# SCH_project_BMO_2026-04-16.net
KiCad netlist of a schematic drawn in EasyEDA
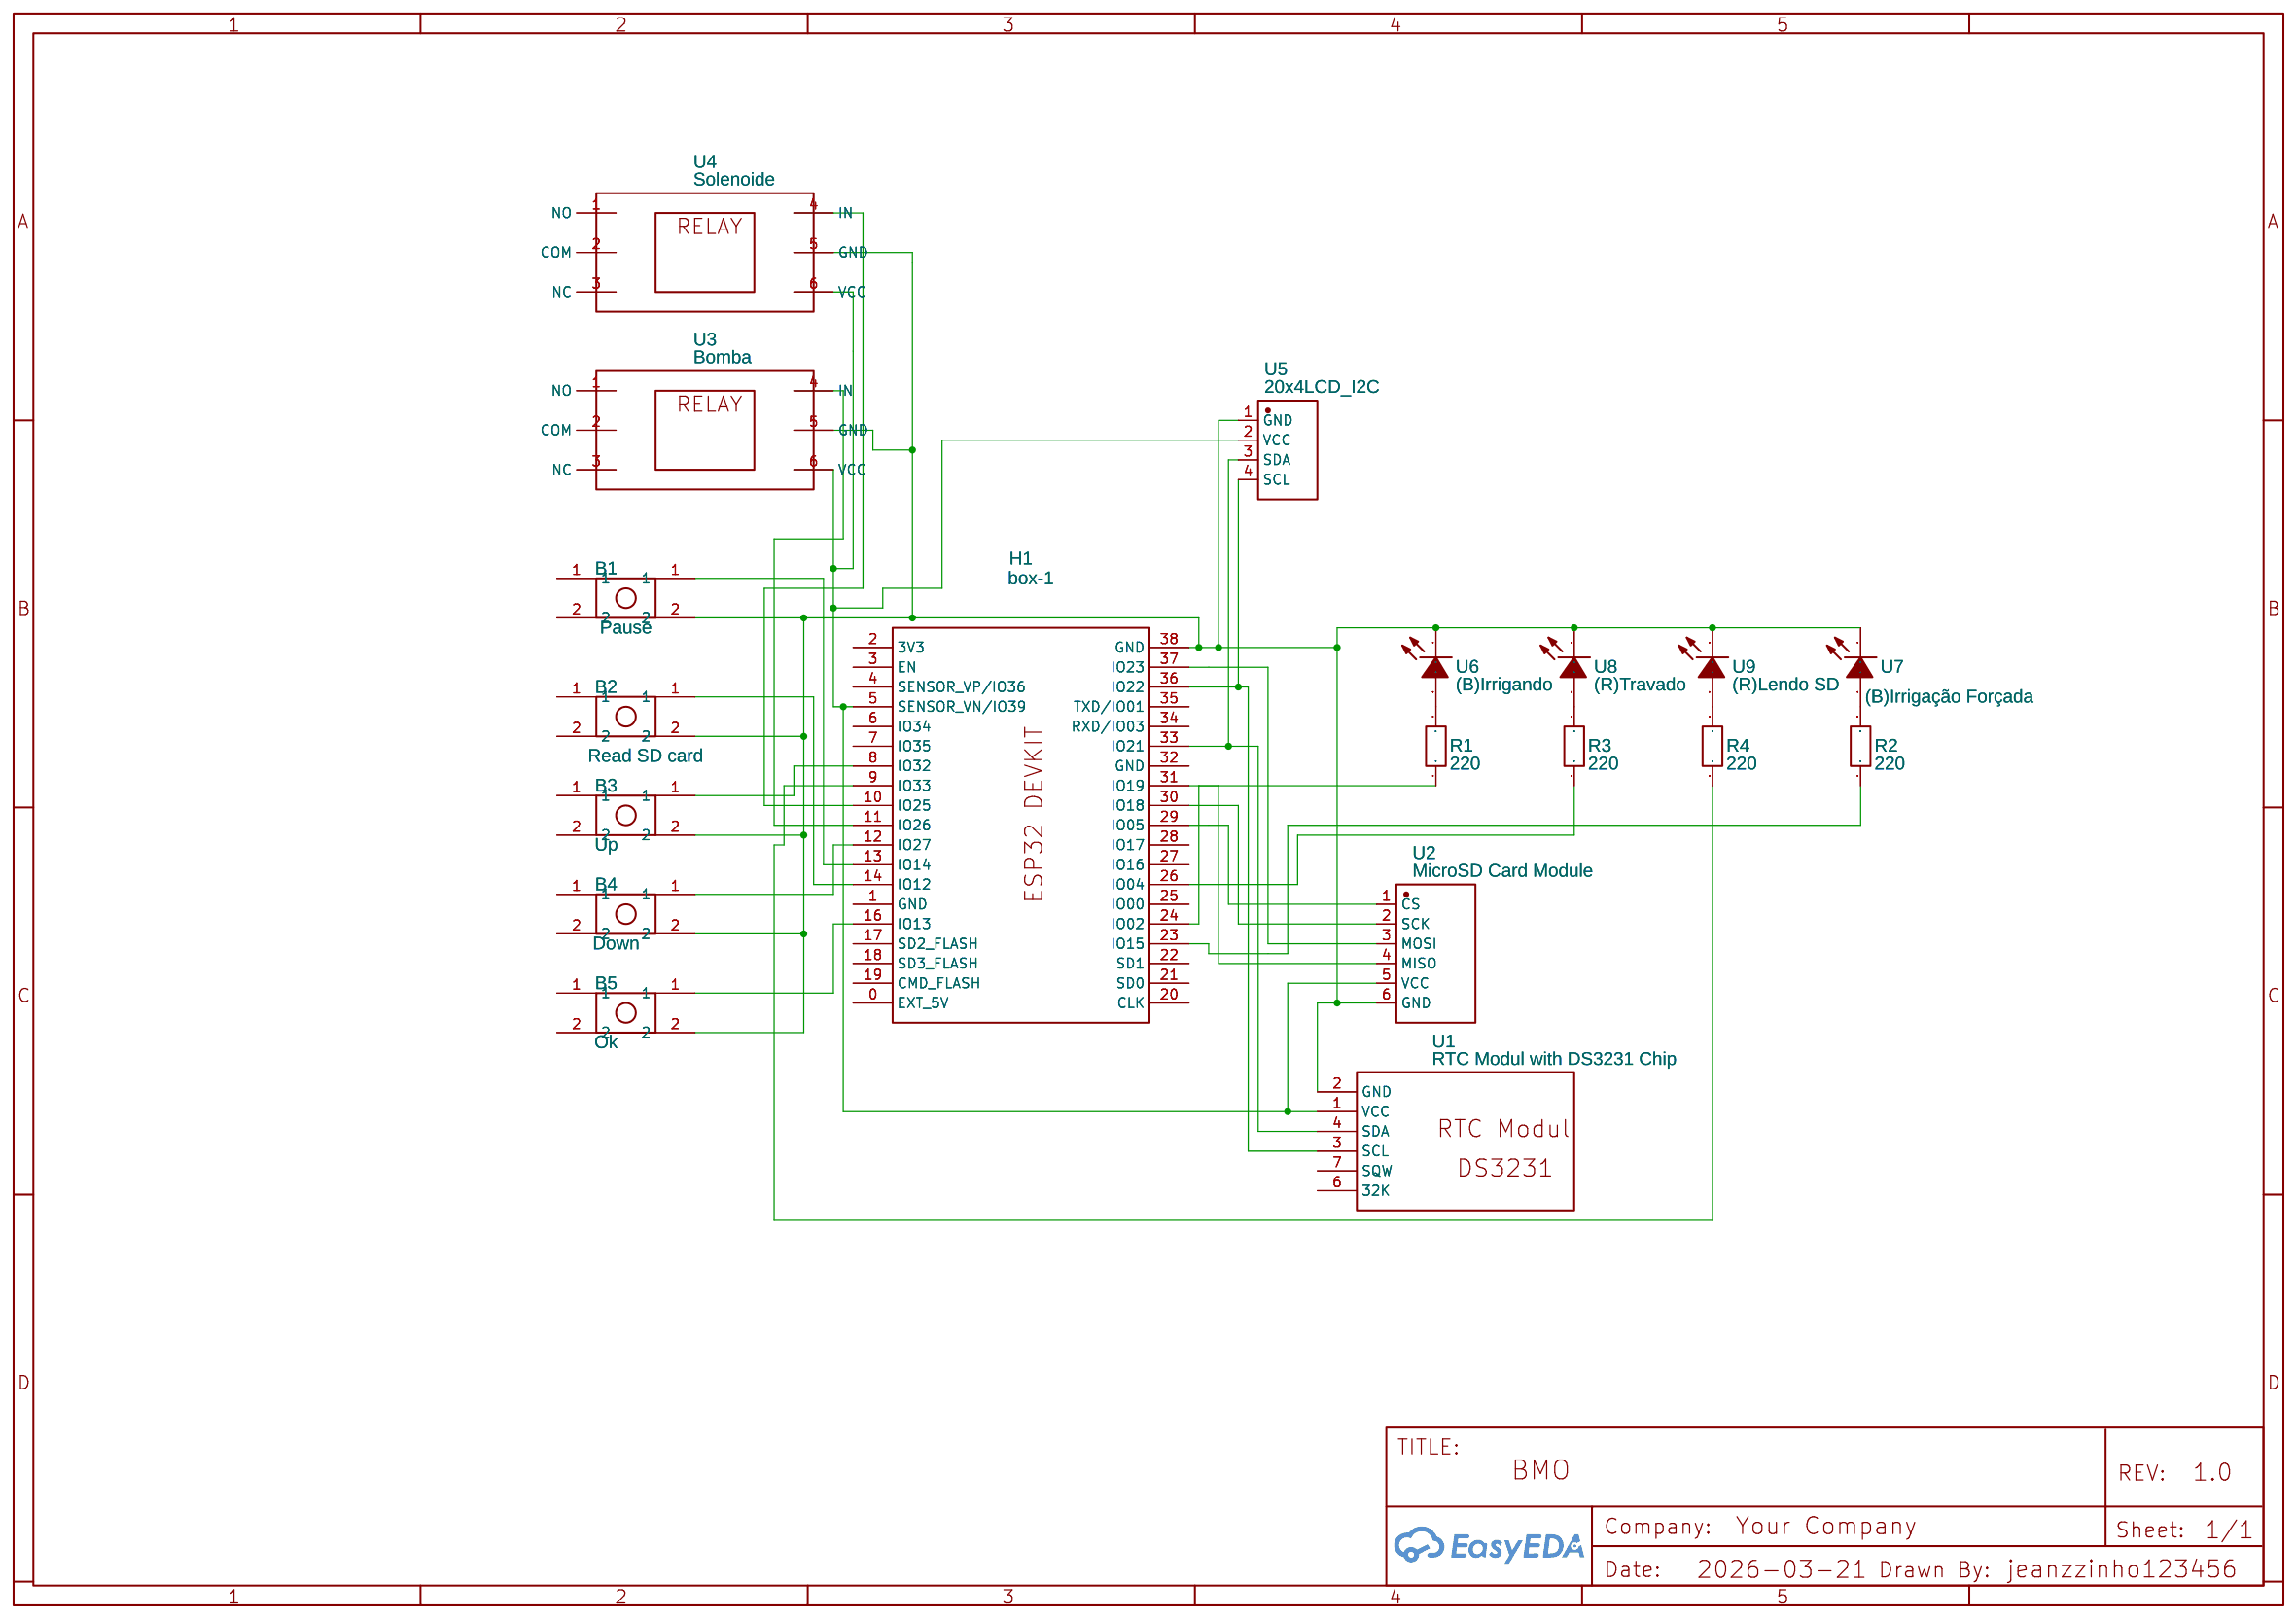
[diagram p0: Sheet_1]
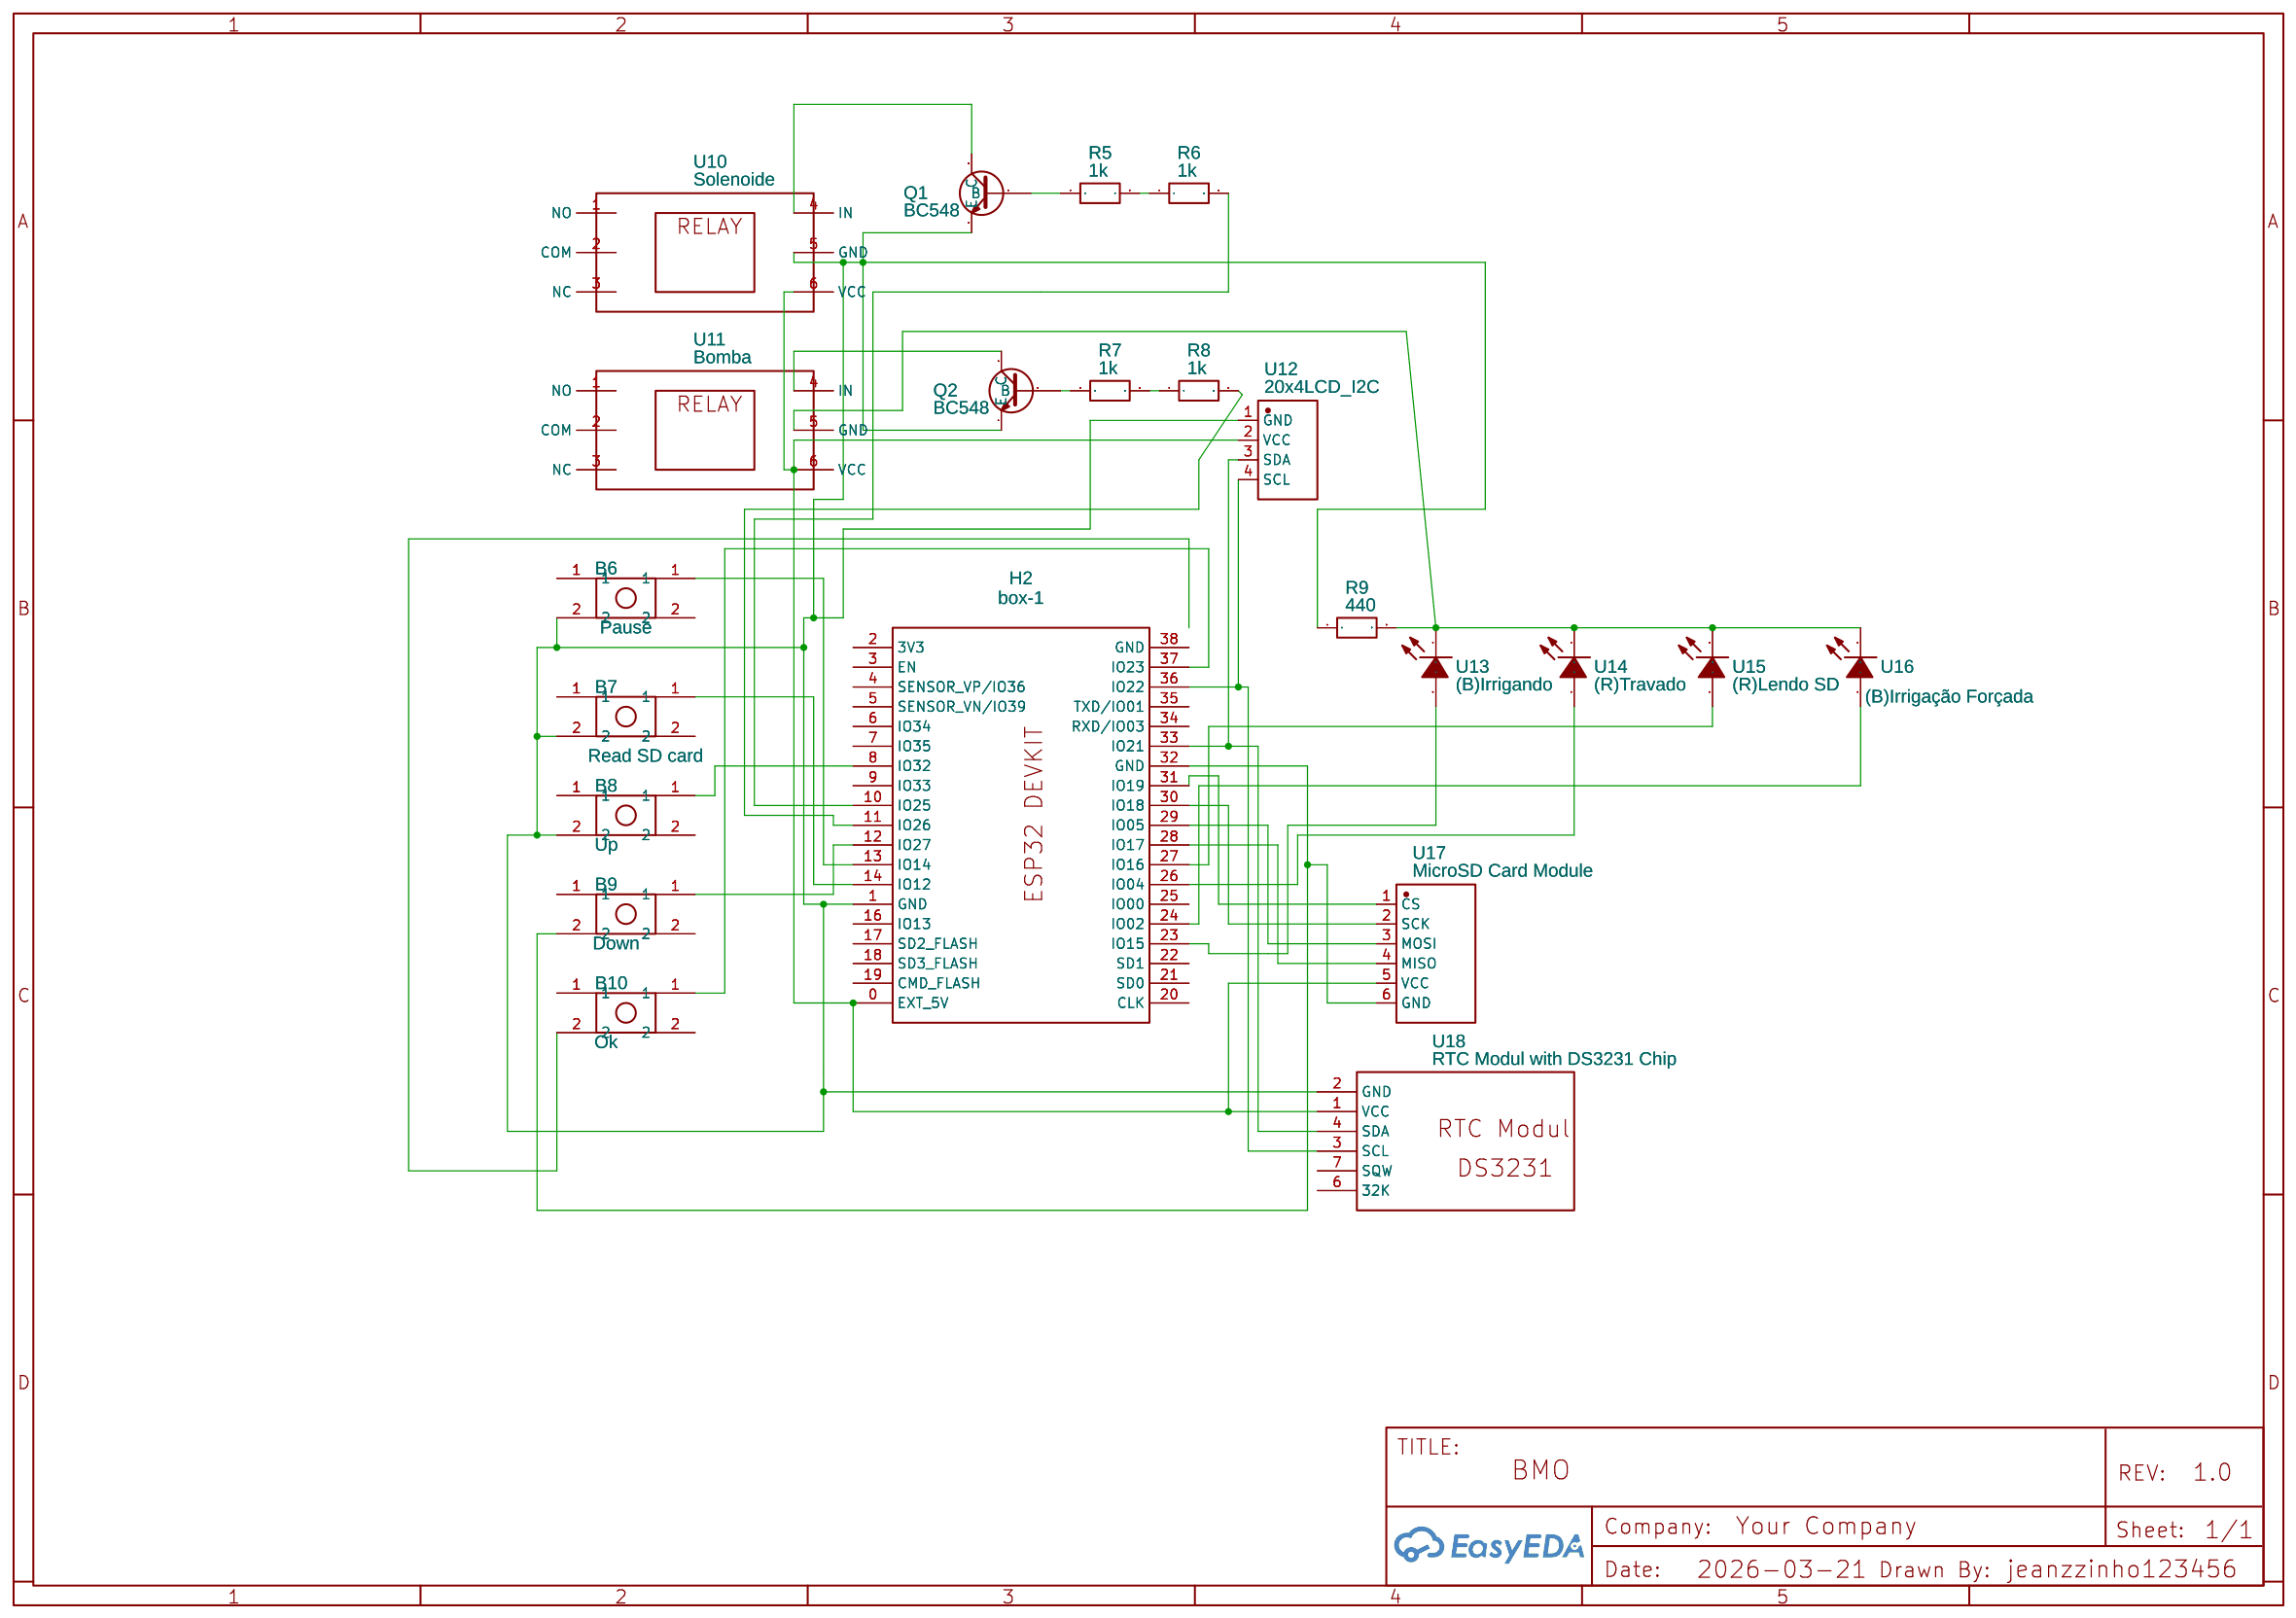
[diagram p1: 1L_BMOSheet_2]

(export (version "E")
  (design (tool "Eeschema 10.0.6"))
  (components
    (comp (ref "B1") (value "Pause") (libsource (lib "") (part "Push-buttom smd 6x6")))
    (comp (ref "B2") (value "Read SD card") (libsource (lib "") (part "Push-buttom smd 6x6")))
    (comp (ref "B3") (value "Up") (libsource (lib "") (part "Push-buttom smd 6x6")))
    (comp (ref "B4") (value "Down") (libsource (lib "") (part "Push-buttom smd 6x6")))
    (comp (ref "B5") (value "Ok") (libsource (lib "") (part "Push-buttom smd 6x6")))
    (comp (ref "H1")
      (value "box-1")
      (fields
        (field (name "Manufacturer Part") "2.54mm 1*19P Female header")
        (field (name "Manufacturer") "BOOMELE")
      )
      (libsource (lib "") (part "box-1"))
    )
    (comp (ref "R1") (value "220") (libsource (lib "") (part "R_0603_EU")))
    (comp (ref "R2") (value "220") (libsource (lib "") (part "R_0603_EU")))
    (comp (ref "R3") (value "220") (libsource (lib "") (part "R_0603_EU")))
    (comp (ref "R4") (value "220") (libsource (lib "") (part "R_0603_EU")))
    (comp (ref "U1")
      (value "RTC Modul with DS3231 Chip")
      (libsource (lib "") (part "RTC Modul with DS3231 Chip"))
    )
    (comp (ref "U2") (value "MicroSD Card Module") (libsource (lib "") (part "MicroSD Card Module")))
    (comp (ref "U3") (value "Bomba") (libsource (lib "") (part "1 CHANNEL RELAY MODULE")))
    (comp (ref "U4") (value "Solenoide") (libsource (lib "") (part "1 CHANNEL RELAY MODULE")))
    (comp (ref "U5") (value "20x4LCD_I2C") (libsource (lib "") (part "20x4LCD_I2C")))
    (comp (ref "U6")
      (value "(B)Irrigando")
      (fields (field (name "Manufacturer Part") "720-LCGH9RNMXNX1"))
      (libsource (lib "") (part "720-LCGH9RNMXNX1"))
    )
    (comp (ref "U7")
      (value "(B)Irrigação Forçada")
      (fields (field (name "Manufacturer Part") "720-LCGH9RNMXNX1"))
      (libsource (lib "") (part "720-LCGH9RNMXNX1"))
    )
    (comp (ref "U8")
      (value "(R)Travado")
      (fields (field (name "Manufacturer Part") "720-LCGH9RNMXNX1"))
      (libsource (lib "") (part "720-LCGH9RNMXNX1"))
    )
    (comp (ref "U9")
      (value "(R)Lendo SD")
      (fields (field (name "Manufacturer Part") "720-LCGH9RNMXNX1"))
      (libsource (lib "") (part "720-LCGH9RNMXNX1"))
    )
    (comp (ref "B6") (value "Pause") (libsource (lib "") (part "Push-buttom smd 6x6")))
    (comp (ref "B7") (value "Read SD card") (libsource (lib "") (part "Push-buttom smd 6x6")))
    (comp (ref "B8") (value "Up") (libsource (lib "") (part "Push-buttom smd 6x6")))
    (comp (ref "B9") (value "Down") (libsource (lib "") (part "Push-buttom smd 6x6")))
    (comp (ref "B10") (value "Ok") (libsource (lib "") (part "Push-buttom smd 6x6")))
    (comp (ref "H2")
      (value "box-1")
      (fields
        (field (name "Manufacturer Part") "2.54mm 1*19P Female header")
        (field (name "Manufacturer") "BOOMELE")
      )
      (libsource (lib "") (part "box-1"))
    )
    (comp (ref "Q1") (value "BC548") (libsource (lib "") (part "TRANSISTOR NPN CBE")))
    (comp (ref "Q2") (value "BC548") (libsource (lib "") (part "TRANSISTOR NPN CBE")))
    (comp (ref "R5") (value "1k") (libsource (lib "") (part "R_0603_EU")))
    (comp (ref "R6") (value "1k") (libsource (lib "") (part "R_0603_EU")))
    (comp (ref "R7") (value "1k") (libsource (lib "") (part "R_0603_EU")))
    (comp (ref "R8") (value "1k") (libsource (lib "") (part "R_0603_EU")))
    (comp (ref "R9") (value "440") (libsource (lib "") (part "R_0603_EU")))
    (comp (ref "U10") (value "Solenoide") (libsource (lib "") (part "1 CHANNEL RELAY MODULE")))
    (comp (ref "U11") (value "Bomba") (libsource (lib "") (part "1 CHANNEL RELAY MODULE")))
    (comp (ref "U12") (value "20x4LCD_I2C") (libsource (lib "") (part "20x4LCD_I2C")))
    (comp (ref "U13")
      (value "(B)Irrigando")
      (fields (field (name "Manufacturer Part") "720-LCGH9RNMXNX1"))
      (libsource (lib "") (part "720-LCGH9RNMXNX1"))
    )
    (comp (ref "U14")
      (value "(R)Travado")
      (fields (field (name "Manufacturer Part") "720-LCGH9RNMXNX1"))
      (libsource (lib "") (part "720-LCGH9RNMXNX1"))
    )
    (comp (ref "U15")
      (value "(R)Lendo SD")
      (fields (field (name "Manufacturer Part") "720-LCGH9RNMXNX1"))
      (libsource (lib "") (part "720-LCGH9RNMXNX1"))
    )
    (comp (ref "U16")
      (value "(B)Irrigação Forçada")
      (fields (field (name "Manufacturer Part") "720-LCGH9RNMXNX1"))
      (libsource (lib "") (part "720-LCGH9RNMXNX1"))
    )
    (comp (ref "U17") (value "MicroSD Card Module") (libsource (lib "") (part "MicroSD Card Module")))
    (comp (ref "U18")
      (value "RTC Modul with DS3231 Chip")
      (libsource (lib "") (part "RTC Modul with DS3231 Chip"))
    )
  )
  (nets
    (net (code "1") (name "Net-(H1-IO02)") (class "Default")
      (node (ref "H1") (pin "24") (pinfunction "IO02_24") (pintype "bidirectional"))
      (node (ref "R1") (pin "1") (pinfunction "1_1") (pintype "unspecified"))
    )
    (net (code "2") (name "Net-(H1-IO04)") (class "Default")
      (node (ref "H1") (pin "26") (pinfunction "IO04_26") (pintype "bidirectional"))
      (node (ref "R3") (pin "1") (pinfunction "1_1") (pintype "unspecified"))
    )
    (net (code "3") (name "Net-(H1-IO05)") (class "Default")
      (node (ref "H1") (pin "29") (pinfunction "IO05_29") (pintype "bidirectional"))
      (node (ref "U2") (pin "1") (pinfunction "CS_1") (pintype "unspecified"))
    )
    (net (code "4") (name "Net-(H1-IO12)") (class "Default")
      (node (ref "B2") (pin "1") (pinfunction "1_1") (pintype "output"))
      (node (ref "H1") (pin "14") (pinfunction "IO12_14") (pintype "bidirectional"))
    )
    (net (code "5") (name "Net-(H1-IO13)") (class "Default")
      (node (ref "B5") (pin "1") (pinfunction "1_1") (pintype "output"))
      (node (ref "H1") (pin "16") (pinfunction "IO13_16") (pintype "bidirectional"))
    )
    (net (code "6") (name "Net-(H1-IO14)") (class "Default")
      (node (ref "B1") (pin "1") (pinfunction "1_1") (pintype "output"))
      (node (ref "H1") (pin "13") (pinfunction "IO14_13") (pintype "bidirectional"))
    )
    (net (code "7") (name "Net-(H1-IO15)") (class "Default")
      (node (ref "H1") (pin "23") (pinfunction "IO15_23") (pintype "bidirectional"))
      (node (ref "R2") (pin "1") (pinfunction "1_1") (pintype "unspecified"))
    )
    (net (code "8") (name "Net-(H1-IO18)") (class "Default")
      (node (ref "H1") (pin "30") (pinfunction "IO18_30") (pintype "bidirectional"))
      (node (ref "U2") (pin "2") (pinfunction "SCK_2") (pintype "unspecified"))
    )
    (net (code "9") (name "Net-(H1-IO19)") (class "Default")
      (node (ref "H1") (pin "31") (pinfunction "IO19_31") (pintype "bidirectional"))
      (node (ref "U2") (pin "4") (pinfunction "MISO_4") (pintype "unspecified"))
    )
    (net (code "10") (name "Net-(H1-IO21)") (class "Default")
      (node (ref "H1") (pin "33") (pinfunction "IO21_33") (pintype "bidirectional"))
      (node (ref "U1") (pin "4") (pinfunction "SDA_4") (pintype "unspecified"))
      (node (ref "U5") (pin "3") (pinfunction "SDA_3") (pintype "unspecified"))
    )
    (net (code "11") (name "Net-(H1-IO22)") (class "Default")
      (node (ref "H1") (pin "36") (pinfunction "IO22_36") (pintype "bidirectional"))
      (node (ref "U1") (pin "3") (pinfunction "SCL_3") (pintype "unspecified"))
      (node (ref "U5") (pin "4") (pinfunction "SCL_4") (pintype "unspecified"))
    )
    (net (code "12") (name "Net-(H1-IO23)") (class "Default")
      (node (ref "H1") (pin "37") (pinfunction "IO23_37") (pintype "bidirectional"))
      (node (ref "U2") (pin "3") (pinfunction "MOSI_3") (pintype "unspecified"))
    )
    (net (code "13") (name "Net-(H1-IO25)") (class "Default")
      (node (ref "H1") (pin "10") (pinfunction "IO25_10") (pintype "bidirectional"))
      (node (ref "U4") (pin "4") (pinfunction "IN_4") (pintype "unspecified"))
    )
    (net (code "14") (name "Net-(H1-IO26)") (class "Default")
      (node (ref "H1") (pin "11") (pinfunction "IO26_11") (pintype "bidirectional"))
      (node (ref "U3") (pin "4") (pinfunction "IN_4") (pintype "unspecified"))
    )
    (net (code "15") (name "Net-(H1-IO27)") (class "Default")
      (node (ref "B4") (pin "1") (pinfunction "1_1") (pintype "output"))
      (node (ref "H1") (pin "12") (pinfunction "IO27_12") (pintype "bidirectional"))
    )
    (net (code "16") (name "Net-(H1-IO32)") (class "Default")
      (node (ref "B3") (pin "1") (pinfunction "1_1") (pintype "output"))
      (node (ref "H1") (pin "8") (pinfunction "IO32_8") (pintype "bidirectional"))
    )
    (net (code "17") (name "Net-(H1-IO33)") (class "Default")
      (node (ref "H1") (pin "9") (pinfunction "IO33_9") (pintype "bidirectional"))
      (node (ref "R4") (pin "1") (pinfunction "1_1") (pintype "unspecified"))
    )
    (net (code "18") (name "Net-(H1-SENSOR_VN{slash}IO39)") (class "Default")
      (node (ref "H1") (pin "5") (pinfunction "SENSOR_VN/IO39_5") (pintype "bidirectional"))
      (node (ref "U1") (pin "1") (pinfunction "VCC_1") (pintype "unspecified"))
      (node (ref "U2") (pin "5") (pinfunction "VCC_5") (pintype "unspecified"))
      (node (ref "U3") (pin "6") (pinfunction "VCC_6") (pintype "unspecified"))
      (node (ref "U4") (pin "6") (pinfunction "VCC_6") (pintype "unspecified"))
      (node (ref "U5") (pin "2") (pinfunction "VCC_2") (pintype "unspecified"))
    )
    (net (code "19") (name "Net-(H2-EXT_5V)") (class "Default")
      (node (ref "H2") (pin "0") (pinfunction "EXT_5V_0") (pintype "passive"))
      (node (ref "U10") (pin "6") (pinfunction "VCC_6") (pintype "unspecified"))
      (node (ref "U11") (pin "6") (pinfunction "VCC_6") (pintype "unspecified"))
      (node (ref "U12") (pin "2") (pinfunction "VCC_2") (pintype "unspecified"))
      (node (ref "U17") (pin "5") (pinfunction "VCC_5") (pintype "unspecified"))
      (node (ref "U18") (pin "1") (pinfunction "VCC_1") (pintype "unspecified"))
    )
    (net (code "20") (name "Net-(H2-IO02)") (class "Default")
      (node (ref "H2") (pin "23") (pinfunction "IO15_23") (pintype "bidirectional"))
      (node (ref "H2") (pin "24") (pinfunction "IO02_24") (pintype "bidirectional"))
      (node (ref "U13") (pin "2") (pinfunction "A_2") (pintype "unspecified"))
      (node (ref "U16") (pin "2") (pinfunction "A_2") (pintype "unspecified"))
    )
    (net (code "21") (name "Net-(H2-IO04)") (class "Default")
      (node (ref "H2") (pin "26") (pinfunction "IO04_26") (pintype "bidirectional"))
      (node (ref "U14") (pin "2") (pinfunction "A_2") (pintype "unspecified"))
    )
    (net (code "22") (name "Net-(H2-IO05)") (class "Default")
      (node (ref "H2") (pin "29") (pinfunction "IO05_29") (pintype "bidirectional"))
      (node (ref "U17") (pin "3") (pinfunction "MOSI_3") (pintype "unspecified"))
    )
    (net (code "23") (name "Net-(H2-IO12)") (class "Default")
      (node (ref "B7") (pin "1") (pinfunction "1_1") (pintype "output"))
      (node (ref "H2") (pin "14") (pinfunction "IO12_14") (pintype "bidirectional"))
    )
    (net (code "24") (name "Net-(H2-IO14)") (class "Default")
      (node (ref "B6") (pin "1") (pinfunction "1_1") (pintype "output"))
      (node (ref "H2") (pin "13") (pinfunction "IO14_13") (pintype "bidirectional"))
    )
    (net (code "25") (name "Net-(H2-IO16)") (class "Default")
      (node (ref "H2") (pin "27") (pinfunction "IO16_27") (pintype "bidirectional"))
      (node (ref "U15") (pin "2") (pinfunction "A_2") (pintype "unspecified"))
    )
    (net (code "26") (name "Net-(H2-IO17)") (class "Default")
      (node (ref "H2") (pin "28") (pinfunction "IO17_28") (pintype "bidirectional"))
      (node (ref "U17") (pin "4") (pinfunction "MISO_4") (pintype "unspecified"))
    )
    (net (code "27") (name "Net-(H2-IO18)") (class "Default")
      (node (ref "H2") (pin "30") (pinfunction "IO18_30") (pintype "bidirectional"))
      (node (ref "U17") (pin "2") (pinfunction "SCK_2") (pintype "unspecified"))
    )
    (net (code "28") (name "Net-(H2-IO19)") (class "Default")
      (node (ref "H2") (pin "31") (pinfunction "IO19_31") (pintype "bidirectional"))
      (node (ref "U17") (pin "1") (pinfunction "CS_1") (pintype "unspecified"))
    )
    (net (code "29") (name "Net-(H2-IO21)") (class "Default")
      (node (ref "H2") (pin "33") (pinfunction "IO21_33") (pintype "bidirectional"))
      (node (ref "U12") (pin "3") (pinfunction "SDA_3") (pintype "unspecified"))
      (node (ref "U18") (pin "4") (pinfunction "SDA_4") (pintype "unspecified"))
    )
    (net (code "30") (name "Net-(H2-IO22)") (class "Default")
      (node (ref "H2") (pin "36") (pinfunction "IO22_36") (pintype "bidirectional"))
      (node (ref "U12") (pin "4") (pinfunction "SCL_4") (pintype "unspecified"))
      (node (ref "U18") (pin "3") (pinfunction "SCL_3") (pintype "unspecified"))
    )
    (net (code "31") (name "Net-(H2-IO23)") (class "Default")
      (node (ref "B10") (pin "1") (pinfunction "1_1") (pintype "output"))
      (node (ref "H2") (pin "37") (pinfunction "IO23_37") (pintype "bidirectional"))
    )
    (net (code "32") (name "Net-(H2-IO25)") (class "Default")
      (node (ref "H2") (pin "10") (pinfunction "IO25_10") (pintype "bidirectional"))
      (node (ref "R6") (pin "2") (pinfunction "2_2") (pintype "unspecified"))
    )
    (net (code "33") (name "Net-(H2-IO26)") (class "Default")
      (node (ref "H2") (pin "11") (pinfunction "IO26_11") (pintype "bidirectional"))
      (node (ref "R8") (pin "2") (pinfunction "2_2") (pintype "unspecified"))
    )
    (net (code "34") (name "Net-(H2-IO27)") (class "Default")
      (node (ref "B9") (pin "1") (pinfunction "1_1") (pintype "output"))
      (node (ref "H2") (pin "12") (pinfunction "IO27_12") (pintype "bidirectional"))
    )
    (net (code "35") (name "Net-(H2-IO32)") (class "Default")
      (node (ref "B8") (pin "1") (pinfunction "1_1") (pintype "output"))
      (node (ref "H2") (pin "8") (pinfunction "IO32_8") (pintype "bidirectional"))
    )
    (net (code "36") (name "Net-(Q1-B)") (class "Default")
      (node (ref "Q1") (pin "2") (pinfunction "B_2") (pintype "input"))
      (node (ref "R5") (pin "1") (pinfunction "1_1") (pintype "unspecified"))
    )
    (net (code "37") (name "Net-(Q1-C)") (class "Default")
      (node (ref "Q1") (pin "3") (pinfunction "C_3") (pintype "unspecified"))
      (node (ref "U10") (pin "4") (pinfunction "IN_4") (pintype "unspecified"))
    )
    (net (code "38") (name "Net-(Q1-E)") (class "Default")
      (node (ref "B6") (pin "2") (pinfunction "2_2") (pintype "input"))
      (node (ref "B7") (pin "2") (pinfunction "2_2") (pintype "input"))
      (node (ref "B8") (pin "2") (pinfunction "2_2") (pintype "input"))
      (node (ref "H2") (pin "1") (pinfunction "GND_1") (pintype "passive"))
      (node (ref "Q1") (pin "1") (pinfunction "E_1") (pintype "unspecified"))
      (node (ref "Q2") (pin "1") (pinfunction "E_1") (pintype "unspecified"))
      (node (ref "R9") (pin "1") (pinfunction "1_1") (pintype "unspecified"))
      (node (ref "U10") (pin "5") (pinfunction "GND_5") (pintype "unspecified"))
      (node (ref "U12") (pin "1") (pinfunction "GND_1") (pintype "unspecified"))
      (node (ref "U18") (pin "2") (pinfunction "GND_2") (pintype "unspecified"))
    )
    (net (code "39") (name "Net-(Q2-B)") (class "Default")
      (node (ref "Q2") (pin "2") (pinfunction "B_2") (pintype "input"))
      (node (ref "R7") (pin "1") (pinfunction "1_1") (pintype "unspecified"))
    )
    (net (code "40") (name "Net-(Q2-C)") (class "Default")
      (node (ref "Q2") (pin "3") (pinfunction "C_3") (pintype "unspecified"))
      (node (ref "U11") (pin "4") (pinfunction "IN_4") (pintype "unspecified"))
    )
    (net (code "41") (name "Net-(R5-Pad2)") (class "Default")
      (node (ref "R5") (pin "2") (pinfunction "2_2") (pintype "unspecified"))
      (node (ref "R6") (pin "1") (pinfunction "1_1") (pintype "unspecified"))
    )
    (net (code "42") (name "Net-(R7-Pad2)") (class "Default")
      (node (ref "R7") (pin "2") (pinfunction "2_2") (pintype "unspecified"))
      (node (ref "R8") (pin "1") (pinfunction "1_1") (pintype "unspecified"))
    )
    (net (code "43") (name "Net-(U1-GND)") (class "Default")
      (node (ref "B1") (pin "2") (pinfunction "2_2") (pintype "output"))
      (node (ref "B2") (pin "2") (pinfunction "2_2") (pintype "output"))
      (node (ref "B3") (pin "2") (pinfunction "2_2") (pintype "output"))
      (node (ref "B4") (pin "2") (pinfunction "2_2") (pintype "output"))
      (node (ref "B5") (pin "2") (pinfunction "2_2") (pintype "output"))
      (node (ref "H1") (pin "38") (pinfunction "GND_38") (pintype "passive"))
      (node (ref "U1") (pin "2") (pinfunction "GND_2") (pintype "unspecified"))
      (node (ref "U2") (pin "6") (pinfunction "GND_6") (pintype "unspecified"))
      (node (ref "U3") (pin "5") (pinfunction "GND_5") (pintype "unspecified"))
      (node (ref "U4") (pin "5") (pinfunction "GND_5") (pintype "unspecified"))
      (node (ref "U5") (pin "1") (pinfunction "GND_1") (pintype "unspecified"))
      (node (ref "U6") (pin "1") (pinfunction "K_1") (pintype "unspecified"))
      (node (ref "U7") (pin "1") (pinfunction "K_1") (pintype "unspecified"))
      (node (ref "U8") (pin "1") (pinfunction "K_1") (pintype "unspecified"))
      (node (ref "U9") (pin "1") (pinfunction "K_1") (pintype "unspecified"))
    )
    (net (code "44") (name "Net-(U6-A)") (class "Default")
      (node (ref "R1") (pin "2") (pinfunction "2_2") (pintype "unspecified"))
      (node (ref "U6") (pin "2") (pinfunction "A_2") (pintype "unspecified"))
    )
    (net (code "45") (name "Net-(U7-A)") (class "Default")
      (node (ref "R2") (pin "2") (pinfunction "2_2") (pintype "unspecified"))
      (node (ref "U7") (pin "2") (pinfunction "A_2") (pintype "unspecified"))
    )
    (net (code "46") (name "Net-(U8-A)") (class "Default")
      (node (ref "R3") (pin "2") (pinfunction "2_2") (pintype "unspecified"))
      (node (ref "U8") (pin "2") (pinfunction "A_2") (pintype "unspecified"))
    )
    (net (code "47") (name "Net-(U9-A)") (class "Default")
      (node (ref "R4") (pin "2") (pinfunction "2_2") (pintype "unspecified"))
      (node (ref "U9") (pin "2") (pinfunction "A_2") (pintype "unspecified"))
    )
    (net (code "48") (name "Net-(U11-GND)") (class "Default")
      (node (ref "R9") (pin "2") (pinfunction "2_2") (pintype "unspecified"))
      (node (ref "U11") (pin "5") (pinfunction "GND_5") (pintype "unspecified"))
      (node (ref "U13") (pin "1") (pinfunction "K_1") (pintype "unspecified"))
      (node (ref "U14") (pin "1") (pinfunction "K_1") (pintype "unspecified"))
      (node (ref "U15") (pin "1") (pinfunction "K_1") (pintype "unspecified"))
      (node (ref "U16") (pin "1") (pinfunction "K_1") (pintype "unspecified"))
    )
    (net (code "49") (name "Net-(U17-GND)") (class "Default")
      (node (ref "B9") (pin "2") (pinfunction "2_2") (pintype "input"))
      (node (ref "H2") (pin "32") (pinfunction "GND_32") (pintype "passive"))
      (node (ref "U17") (pin "6") (pinfunction "GND_6") (pintype "unspecified"))
    )
    (net (code "50") (name "unconnected-(B1-Pad1)") (class "Default")
      (node (ref "B1") (pin "1") (pinfunction "1_1") (pintype "input"))
    )
    (net (code "51") (name "unconnected-(B1-Pad2)") (class "Default")
      (node (ref "B1") (pin "2") (pinfunction "2_2") (pintype "input"))
    )
    (net (code "52") (name "unconnected-(B2-Pad1)") (class "Default")
      (node (ref "B2") (pin "1") (pinfunction "1_1") (pintype "input"))
    )
    (net (code "53") (name "unconnected-(B2-Pad2)") (class "Default")
      (node (ref "B2") (pin "2") (pinfunction "2_2") (pintype "input"))
    )
    (net (code "54") (name "unconnected-(B3-Pad1)") (class "Default")
      (node (ref "B3") (pin "1") (pinfunction "1_1") (pintype "input"))
    )
    (net (code "55") (name "unconnected-(B3-Pad2)") (class "Default")
      (node (ref "B3") (pin "2") (pinfunction "2_2") (pintype "input"))
    )
    (net (code "56") (name "unconnected-(B4-Pad1)") (class "Default")
      (node (ref "B4") (pin "1") (pinfunction "1_1") (pintype "input"))
    )
    (net (code "57") (name "unconnected-(B4-Pad2)") (class "Default")
      (node (ref "B4") (pin "2") (pinfunction "2_2") (pintype "input"))
    )
    (net (code "58") (name "unconnected-(B5-Pad1)") (class "Default")
      (node (ref "B5") (pin "1") (pinfunction "1_1") (pintype "input"))
    )
    (net (code "59") (name "unconnected-(B5-Pad2)") (class "Default")
      (node (ref "B5") (pin "2") (pinfunction "2_2") (pintype "input"))
    )
    (net (code "60") (name "unconnected-(B6-Pad1)") (class "Default")
      (node (ref "B6") (pin "1") (pinfunction "1_1") (pintype "input"))
    )
    (net (code "61") (name "unconnected-(B6-Pad2)") (class "Default")
      (node (ref "B6") (pin "2") (pinfunction "2_2") (pintype "output"))
    )
    (net (code "62") (name "unconnected-(B7-Pad1)") (class "Default")
      (node (ref "B7") (pin "1") (pinfunction "1_1") (pintype "input"))
    )
    (net (code "63") (name "unconnected-(B7-Pad2)") (class "Default")
      (node (ref "B7") (pin "2") (pinfunction "2_2") (pintype "output"))
    )
    (net (code "64") (name "unconnected-(B8-Pad1)") (class "Default")
      (node (ref "B8") (pin "1") (pinfunction "1_1") (pintype "input"))
    )
    (net (code "65") (name "unconnected-(B8-Pad2)") (class "Default")
      (node (ref "B8") (pin "2") (pinfunction "2_2") (pintype "output"))
    )
    (net (code "66") (name "unconnected-(B9-Pad1)") (class "Default")
      (node (ref "B9") (pin "1") (pinfunction "1_1") (pintype "input"))
    )
    (net (code "67") (name "unconnected-(B9-Pad2)") (class "Default")
      (node (ref "B9") (pin "2") (pinfunction "2_2") (pintype "output"))
    )
    (net (code "68") (name "unconnected-(B10-Pad1)") (class "Default")
      (node (ref "B10") (pin "1") (pinfunction "1_1") (pintype "input"))
    )
    (net (code "69") (name "unconnected-(B10-Pad2)") (class "Default")
      (node (ref "B10") (pin "2") (pinfunction "2_2") (pintype "output"))
    )
    (net (code "70") (name "unconnected-(B10-Pad2)_1") (class "Default")
      (node (ref "B10") (pin "2") (pinfunction "2_2") (pintype "input"))
    )
    (net (code "71") (name "unconnected-(H1-3V3-Pad2)") (class "Default")
      (node (ref "H1") (pin "2") (pinfunction "3V3_2") (pintype "passive"))
    )
    (net (code "72") (name "unconnected-(H1-CLK-Pad20)") (class "Default")
      (node (ref "H1") (pin "20") (pinfunction "CLK_20") (pintype "bidirectional"))
    )
    (net (code "73") (name "unconnected-(H1-CMD_FLASH-Pad19)") (class "Default")
      (node (ref "H1") (pin "19") (pinfunction "CMD_FLASH_19") (pintype "bidirectional"))
    )
    (net (code "74") (name "unconnected-(H1-EN-Pad3)") (class "Default")
      (node (ref "H1") (pin "3") (pinfunction "EN_3") (pintype "bidirectional"))
    )
    (net (code "75") (name "unconnected-(H1-EXT_5V-Pad0)") (class "Default")
      (node (ref "H1") (pin "0") (pinfunction "EXT_5V_0") (pintype "passive"))
    )
    (net (code "76") (name "unconnected-(H1-GND-Pad1)") (class "Default")
      (node (ref "H1") (pin "1") (pinfunction "GND_1") (pintype "passive"))
    )
    (net (code "77") (name "unconnected-(H1-GND-Pad32)") (class "Default")
      (node (ref "H1") (pin "32") (pinfunction "GND_32") (pintype "passive"))
    )
    (net (code "78") (name "unconnected-(H1-IO00-Pad25)") (class "Default")
      (node (ref "H1") (pin "25") (pinfunction "IO00_25") (pintype "bidirectional"))
    )
    (net (code "79") (name "unconnected-(H1-IO16-Pad27)") (class "Default")
      (node (ref "H1") (pin "27") (pinfunction "IO16_27") (pintype "bidirectional"))
    )
    (net (code "80") (name "unconnected-(H1-IO17-Pad28)") (class "Default")
      (node (ref "H1") (pin "28") (pinfunction "IO17_28") (pintype "bidirectional"))
    )
    (net (code "81") (name "unconnected-(H1-IO34-Pad6)") (class "Default")
      (node (ref "H1") (pin "6") (pinfunction "IO34_6") (pintype "bidirectional"))
    )
    (net (code "82") (name "unconnected-(H1-IO35-Pad7)") (class "Default")
      (node (ref "H1") (pin "7") (pinfunction "IO35_7") (pintype "bidirectional"))
    )
    (net (code "83") (name "unconnected-(H1-RXD{slash}IO03-Pad34)") (class "Default")
      (node (ref "H1") (pin "34") (pinfunction "RXD/IO03_34") (pintype "bidirectional"))
    )
    (net (code "84") (name "unconnected-(H1-SD0-Pad21)") (class "Default")
      (node (ref "H1") (pin "21") (pinfunction "SD0_21") (pintype "bidirectional"))
    )
    (net (code "85") (name "unconnected-(H1-SD1-Pad22)") (class "Default")
      (node (ref "H1") (pin "22") (pinfunction "SD1_22") (pintype "bidirectional"))
    )
    (net (code "86") (name "unconnected-(H1-SD2_FLASH-Pad17)") (class "Default")
      (node (ref "H1") (pin "17") (pinfunction "SD2_FLASH_17") (pintype "bidirectional"))
    )
    (net (code "87") (name "unconnected-(H1-SD3_FLASH-Pad18)") (class "Default")
      (node (ref "H1") (pin "18") (pinfunction "SD3_FLASH_18") (pintype "bidirectional"))
    )
    (net (code "88") (name "unconnected-(H1-SENSOR_VP{slash}IO36-Pad4)") (class "Default")
      (node (ref "H1") (pin "4") (pinfunction "SENSOR_VP/IO36_4") (pintype "bidirectional"))
    )
    (net (code "89") (name "unconnected-(H1-TXD{slash}IO01-Pad35)") (class "Default")
      (node (ref "H1") (pin "35") (pinfunction "TXD/IO01_35") (pintype "bidirectional"))
    )
    (net (code "90") (name "unconnected-(H2-3V3-Pad2)") (class "Default")
      (node (ref "H2") (pin "2") (pinfunction "3V3_2") (pintype "passive"))
    )
    (net (code "91") (name "unconnected-(H2-CLK-Pad20)") (class "Default")
      (node (ref "H2") (pin "20") (pinfunction "CLK_20") (pintype "bidirectional"))
    )
    (net (code "92") (name "unconnected-(H2-CMD_FLASH-Pad19)") (class "Default")
      (node (ref "H2") (pin "19") (pinfunction "CMD_FLASH_19") (pintype "bidirectional"))
    )
    (net (code "93") (name "unconnected-(H2-EN-Pad3)") (class "Default")
      (node (ref "H2") (pin "3") (pinfunction "EN_3") (pintype "bidirectional"))
    )
    (net (code "94") (name "unconnected-(H2-GND-Pad38)") (class "Default")
      (node (ref "H2") (pin "38") (pinfunction "GND_38") (pintype "passive"))
    )
    (net (code "95") (name "unconnected-(H2-IO00-Pad25)") (class "Default")
      (node (ref "H2") (pin "25") (pinfunction "IO00_25") (pintype "bidirectional"))
    )
    (net (code "96") (name "unconnected-(H2-IO13-Pad16)") (class "Default")
      (node (ref "H2") (pin "16") (pinfunction "IO13_16") (pintype "bidirectional"))
    )
    (net (code "97") (name "unconnected-(H2-IO33-Pad9)") (class "Default")
      (node (ref "H2") (pin "9") (pinfunction "IO33_9") (pintype "bidirectional"))
    )
    (net (code "98") (name "unconnected-(H2-IO34-Pad6)") (class "Default")
      (node (ref "H2") (pin "6") (pinfunction "IO34_6") (pintype "bidirectional"))
    )
    (net (code "99") (name "unconnected-(H2-IO35-Pad7)") (class "Default")
      (node (ref "H2") (pin "7") (pinfunction "IO35_7") (pintype "bidirectional"))
    )
    (net (code "100") (name "unconnected-(H2-RXD{slash}IO03-Pad34)") (class "Default")
      (node (ref "H2") (pin "34") (pinfunction "RXD/IO03_34") (pintype "bidirectional"))
    )
    (net (code "101") (name "unconnected-(H2-SD0-Pad21)") (class "Default")
      (node (ref "H2") (pin "21") (pinfunction "SD0_21") (pintype "bidirectional"))
    )
    (net (code "102") (name "unconnected-(H2-SD1-Pad22)") (class "Default")
      (node (ref "H2") (pin "22") (pinfunction "SD1_22") (pintype "bidirectional"))
    )
    (net (code "103") (name "unconnected-(H2-SD2_FLASH-Pad17)") (class "Default")
      (node (ref "H2") (pin "17") (pinfunction "SD2_FLASH_17") (pintype "bidirectional"))
    )
    (net (code "104") (name "unconnected-(H2-SD3_FLASH-Pad18)") (class "Default")
      (node (ref "H2") (pin "18") (pinfunction "SD3_FLASH_18") (pintype "bidirectional"))
    )
    (net (code "105") (name "unconnected-(H2-SENSOR_VN{slash}IO39-Pad5)") (class "Default")
      (node (ref "H2") (pin "5") (pinfunction "SENSOR_VN/IO39_5") (pintype "bidirectional"))
    )
    (net (code "106") (name "unconnected-(H2-SENSOR_VP{slash}IO36-Pad4)") (class "Default")
      (node (ref "H2") (pin "4") (pinfunction "SENSOR_VP/IO36_4") (pintype "bidirectional"))
    )
    (net (code "107") (name "unconnected-(H2-TXD{slash}IO01-Pad35)") (class "Default")
      (node (ref "H2") (pin "35") (pinfunction "TXD/IO01_35") (pintype "bidirectional"))
    )
    (net (code "108") (name "unconnected-(U1-32K-Pad6)") (class "Default")
      (node (ref "U1") (pin "6") (pinfunction "32K_6") (pintype "unspecified"))
    )
    (net (code "109") (name "unconnected-(U1-SQW-Pad7)") (class "Default")
      (node (ref "U1") (pin "7") (pinfunction "SQW_7") (pintype "unspecified"))
    )
    (net (code "110") (name "unconnected-(U3-COM-Pad2)") (class "Default")
      (node (ref "U3") (pin "2") (pinfunction "COM_2") (pintype "unspecified"))
    )
    (net (code "111") (name "unconnected-(U3-NC-Pad3)") (class "Default")
      (node (ref "U3") (pin "3") (pinfunction "NC_3") (pintype "unspecified"))
    )
    (net (code "112") (name "unconnected-(U3-NO-Pad1)") (class "Default")
      (node (ref "U3") (pin "1") (pinfunction "NO_1") (pintype "unspecified"))
    )
    (net (code "113") (name "unconnected-(U4-COM-Pad2)") (class "Default")
      (node (ref "U4") (pin "2") (pinfunction "COM_2") (pintype "unspecified"))
    )
    (net (code "114") (name "unconnected-(U4-NC-Pad3)") (class "Default")
      (node (ref "U4") (pin "3") (pinfunction "NC_3") (pintype "unspecified"))
    )
    (net (code "115") (name "unconnected-(U4-NO-Pad1)") (class "Default")
      (node (ref "U4") (pin "1") (pinfunction "NO_1") (pintype "unspecified"))
    )
    (net (code "116") (name "unconnected-(U10-COM-Pad2)") (class "Default")
      (node (ref "U10") (pin "2") (pinfunction "COM_2") (pintype "unspecified"))
    )
    (net (code "117") (name "unconnected-(U10-NC-Pad3)") (class "Default")
      (node (ref "U10") (pin "3") (pinfunction "NC_3") (pintype "unspecified"))
    )
    (net (code "118") (name "unconnected-(U10-NO-Pad1)") (class "Default")
      (node (ref "U10") (pin "1") (pinfunction "NO_1") (pintype "unspecified"))
    )
    (net (code "119") (name "unconnected-(U11-COM-Pad2)") (class "Default")
      (node (ref "U11") (pin "2") (pinfunction "COM_2") (pintype "unspecified"))
    )
    (net (code "120") (name "unconnected-(U11-NC-Pad3)") (class "Default")
      (node (ref "U11") (pin "3") (pinfunction "NC_3") (pintype "unspecified"))
    )
    (net (code "121") (name "unconnected-(U11-NO-Pad1)") (class "Default")
      (node (ref "U11") (pin "1") (pinfunction "NO_1") (pintype "unspecified"))
    )
    (net (code "122") (name "unconnected-(U18-32K-Pad6)") (class "Default")
      (node (ref "U18") (pin "6") (pinfunction "32K_6") (pintype "unspecified"))
    )
    (net (code "123") (name "unconnected-(U18-SQW-Pad7)") (class "Default")
      (node (ref "U18") (pin "7") (pinfunction "SQW_7") (pintype "unspecified"))
    )
  )
)
